# Steering_Board.net
KiCad netlist of a schematic drawn in EAGLE
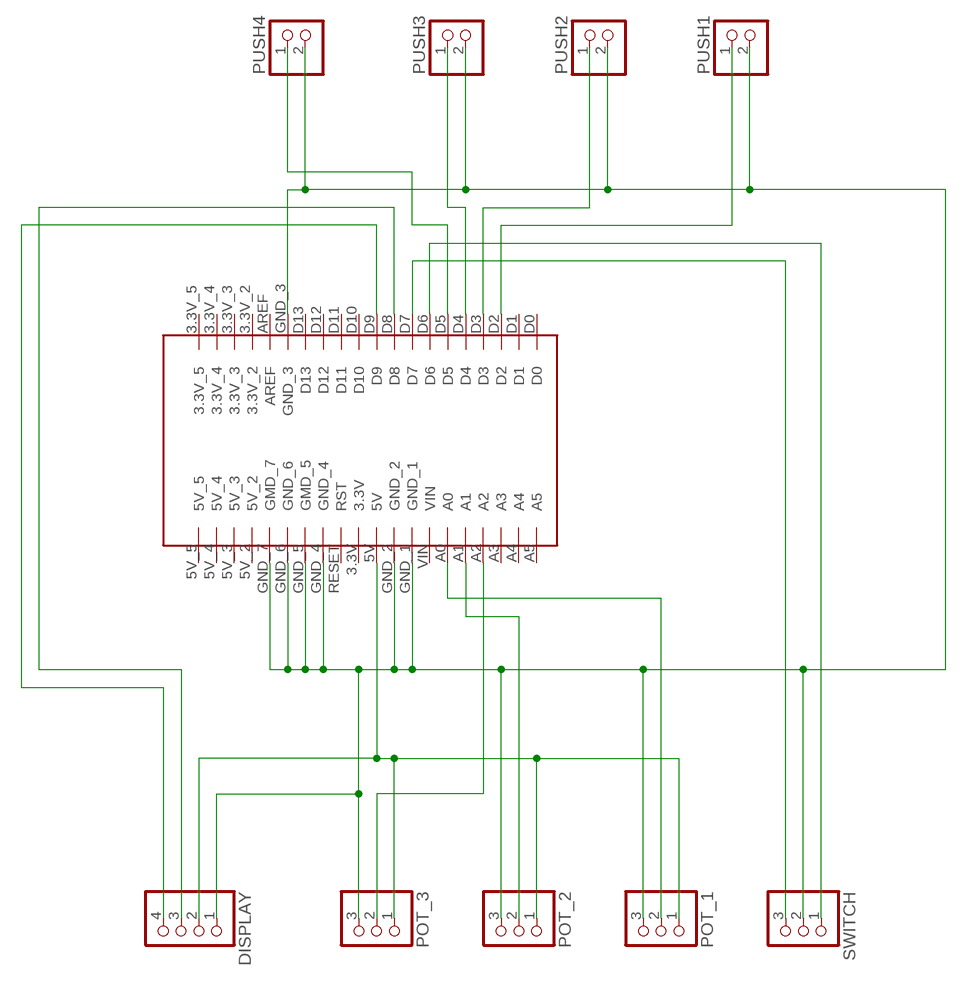
[diagram p0: schematic, sheet 1]

(export (version "E")
  (design (tool "Eeschema 10.0.6"))
  (components
    (comp (ref "2X40CONECTOR1")
      (value "2X40_CONNECTOR")
      (footprint "eagle-import:2X40_PIN_CONNECTOR")
      (libsource (lib "eagle-import") (part "2X40_CONNECTOR"))
    )
    (comp (ref "DISPLAY")
      (value "PINHD-1X4")
      (footprint "eagle-import:1X04")
      (libsource (lib "eagle-import") (part "PINHD-1X4"))
    )
    (comp (ref "POT_1")
      (value "PINHD-1X3")
      (footprint "eagle-import:1X03")
      (libsource (lib "eagle-import") (part "PINHD-1X3"))
    )
    (comp (ref "POT_2")
      (value "PINHD-1X3")
      (footprint "eagle-import:1X03")
      (libsource (lib "eagle-import") (part "PINHD-1X3"))
    )
    (comp (ref "POT_3")
      (value "PINHD-1X3")
      (footprint "eagle-import:1X03")
      (libsource (lib "eagle-import") (part "PINHD-1X3"))
    )
    (comp (ref "PUSH1")
      (value "PINHD-1X2")
      (footprint "eagle-import:1X02")
      (libsource (lib "eagle-import") (part "PINHD-1X2"))
    )
    (comp (ref "PUSH2")
      (value "PINHD-1X2")
      (footprint "eagle-import:1X02")
      (libsource (lib "eagle-import") (part "PINHD-1X2"))
    )
    (comp (ref "PUSH3")
      (value "PINHD-1X2")
      (footprint "eagle-import:1X02")
      (libsource (lib "eagle-import") (part "PINHD-1X2"))
    )
    (comp (ref "PUSH4")
      (value "PINHD-1X2")
      (footprint "eagle-import:1X02")
      (libsource (lib "eagle-import") (part "PINHD-1X2"))
    )
    (comp (ref "SWITCH")
      (value "PINHD-1X3")
      (footprint "eagle-import:1X03")
      (libsource (lib "eagle-import") (part "PINHD-1X3"))
    )
  )
  (nets
    (net (code "1") (name "Net-(2X40CONECTOR1-GMD_5)") (class "Default")
      (node (ref "2X40CONECTOR1") (pin "GND_1") (pinfunction "GND_1_GND_1") (pintype "bidirectional"))
      (node (ref "2X40CONECTOR1") (pin "GND_2") (pinfunction "GND_2_GND_2") (pintype "bidirectional"))
      (node (ref "2X40CONECTOR1") (pin "GND_3") (pinfunction "GND_3_GND_3") (pintype "bidirectional"))
      (node (ref "2X40CONECTOR1") (pin "GND_4") (pinfunction "GND_4_GND_4") (pintype "bidirectional"))
      (node (ref "2X40CONECTOR1") (pin "GND_5") (pinfunction "GMD_5_GND_5") (pintype "bidirectional"))
      (node (ref "2X40CONECTOR1") (pin "GND_6") (pinfunction "GND_6_GND_6") (pintype "bidirectional"))
      (node (ref "2X40CONECTOR1") (pin "GND_7") (pinfunction "GMD_7_GND_7") (pintype "bidirectional"))
      (node (ref "DISPLAY") (pin "1") (pinfunction "1_1") (pintype "passive"))
      (node (ref "POT_1") (pin "3") (pinfunction "3_3") (pintype "passive"))
      (node (ref "POT_2") (pin "3") (pinfunction "3_3") (pintype "passive"))
      (node (ref "POT_3") (pin "3") (pinfunction "3_3") (pintype "passive"))
      (node (ref "PUSH1") (pin "2") (pinfunction "2_2") (pintype "passive"))
      (node (ref "PUSH2") (pin "2") (pinfunction "2_2") (pintype "passive"))
      (node (ref "PUSH3") (pin "2") (pinfunction "2_2") (pintype "passive"))
      (node (ref "PUSH4") (pin "2") (pinfunction "2_2") (pintype "passive"))
      (node (ref "SWITCH") (pin "2") (pinfunction "2_2") (pintype "passive"))
    )
    (net (code "2") (name "Net-(2X40CONECTOR1-Pad5V)") (class "Default")
      (node (ref "2X40CONECTOR1") (pin "5V") (pinfunction "5V_5V") (pintype "bidirectional"))
      (node (ref "DISPLAY") (pin "2") (pinfunction "2_2") (pintype "passive"))
      (node (ref "POT_1") (pin "1") (pinfunction "1_1") (pintype "passive"))
      (node (ref "POT_2") (pin "1") (pinfunction "1_1") (pintype "passive"))
      (node (ref "POT_3") (pin "1") (pinfunction "1_1") (pintype "passive"))
    )
    (net (code "3") (name "Net-(2X40CONECTOR1-PadA0)") (class "Default")
      (node (ref "2X40CONECTOR1") (pin "A0") (pinfunction "A0_A0") (pintype "bidirectional"))
      (node (ref "POT_1") (pin "2") (pinfunction "2_2") (pintype "passive"))
    )
    (net (code "4") (name "Net-(2X40CONECTOR1-PadA1)") (class "Default")
      (node (ref "2X40CONECTOR1") (pin "A1") (pinfunction "A1_A1") (pintype "bidirectional"))
      (node (ref "POT_2") (pin "2") (pinfunction "2_2") (pintype "passive"))
    )
    (net (code "5") (name "Net-(2X40CONECTOR1-PadA2)") (class "Default")
      (node (ref "2X40CONECTOR1") (pin "A2") (pinfunction "A2_A2") (pintype "bidirectional"))
      (node (ref "POT_3") (pin "2") (pinfunction "2_2") (pintype "passive"))
    )
    (net (code "6") (name "Net-(2X40CONECTOR1-PadD2)") (class "Default")
      (node (ref "2X40CONECTOR1") (pin "D2") (pinfunction "D2_D2") (pintype "bidirectional"))
      (node (ref "PUSH1") (pin "1") (pinfunction "1_1") (pintype "passive"))
    )
    (net (code "7") (name "Net-(2X40CONECTOR1-PadD3)") (class "Default")
      (node (ref "2X40CONECTOR1") (pin "D3") (pinfunction "D3_D3") (pintype "bidirectional"))
      (node (ref "PUSH2") (pin "1") (pinfunction "1_1") (pintype "passive"))
    )
    (net (code "8") (name "Net-(2X40CONECTOR1-PadD4)") (class "Default")
      (node (ref "2X40CONECTOR1") (pin "D4") (pinfunction "D4_D4") (pintype "bidirectional"))
      (node (ref "PUSH3") (pin "1") (pinfunction "1_1") (pintype "passive"))
    )
    (net (code "9") (name "Net-(2X40CONECTOR1-PadD5)") (class "Default")
      (node (ref "2X40CONECTOR1") (pin "D5") (pinfunction "D5_D5") (pintype "bidirectional"))
      (node (ref "PUSH4") (pin "1") (pinfunction "1_1") (pintype "passive"))
    )
    (net (code "10") (name "Net-(2X40CONECTOR1-PadD6)") (class "Default")
      (node (ref "2X40CONECTOR1") (pin "D6") (pinfunction "D6_D6") (pintype "bidirectional"))
      (node (ref "SWITCH") (pin "1") (pinfunction "1_1") (pintype "passive"))
    )
    (net (code "11") (name "Net-(2X40CONECTOR1-PadD7)") (class "Default")
      (node (ref "2X40CONECTOR1") (pin "D7") (pinfunction "D7_D7") (pintype "bidirectional"))
      (node (ref "SWITCH") (pin "3") (pinfunction "3_3") (pintype "passive"))
    )
    (net (code "12") (name "Net-(2X40CONECTOR1-PadD8)") (class "Default")
      (node (ref "2X40CONECTOR1") (pin "D8") (pinfunction "D8_D8") (pintype "bidirectional"))
      (node (ref "DISPLAY") (pin "3") (pinfunction "3_3") (pintype "passive"))
    )
    (net (code "13") (name "Net-(2X40CONECTOR1-PadD9)") (class "Default")
      (node (ref "2X40CONECTOR1") (pin "D9") (pinfunction "D9_D9") (pintype "bidirectional"))
      (node (ref "DISPLAY") (pin "4") (pinfunction "4_4") (pintype "passive"))
    )
    (net (code "14") (name "unconnected-(2X40CONECTOR1-Pad3.3V)") (class "Default")
      (node (ref "2X40CONECTOR1") (pin "3.3V") (pinfunction "3.3V_3.3V") (pintype "bidirectional"))
    )
    (net (code "15") (name "unconnected-(2X40CONECTOR1-Pad3.3V_2)") (class "Default")
      (node (ref "2X40CONECTOR1") (pin "3.3V_2") (pinfunction "3.3V_2_3.3V_2") (pintype "bidirectional"))
    )
    (net (code "16") (name "unconnected-(2X40CONECTOR1-Pad3.3V_3)") (class "Default")
      (node (ref "2X40CONECTOR1") (pin "3.3V_3") (pinfunction "3.3V_3_3.3V_3") (pintype "bidirectional"))
    )
    (net (code "17") (name "unconnected-(2X40CONECTOR1-Pad3.3V_4)") (class "Default")
      (node (ref "2X40CONECTOR1") (pin "3.3V_4") (pinfunction "3.3V_4_3.3V_4") (pintype "bidirectional"))
    )
    (net (code "18") (name "unconnected-(2X40CONECTOR1-Pad3.3V_5)") (class "Default")
      (node (ref "2X40CONECTOR1") (pin "3.3V_5") (pinfunction "3.3V_5_3.3V_5") (pintype "bidirectional"))
    )
    (net (code "19") (name "unconnected-(2X40CONECTOR1-Pad5V_2)") (class "Default")
      (node (ref "2X40CONECTOR1") (pin "5V_2") (pinfunction "5V_2_5V_2") (pintype "bidirectional"))
    )
    (net (code "20") (name "unconnected-(2X40CONECTOR1-Pad5V_3)") (class "Default")
      (node (ref "2X40CONECTOR1") (pin "5V_3") (pinfunction "5V_3_5V_3") (pintype "bidirectional"))
    )
    (net (code "21") (name "unconnected-(2X40CONECTOR1-Pad5V_4)") (class "Default")
      (node (ref "2X40CONECTOR1") (pin "5V_4") (pinfunction "5V_4_5V_4") (pintype "bidirectional"))
    )
    (net (code "22") (name "unconnected-(2X40CONECTOR1-Pad5V_5)") (class "Default")
      (node (ref "2X40CONECTOR1") (pin "5V_5") (pinfunction "5V_5_5V_5") (pintype "bidirectional"))
    )
    (net (code "23") (name "unconnected-(2X40CONECTOR1-PadA3)") (class "Default")
      (node (ref "2X40CONECTOR1") (pin "A3") (pinfunction "A3_A3") (pintype "bidirectional"))
    )
    (net (code "24") (name "unconnected-(2X40CONECTOR1-PadA4)") (class "Default")
      (node (ref "2X40CONECTOR1") (pin "A4") (pinfunction "A4_A4") (pintype "bidirectional"))
    )
    (net (code "25") (name "unconnected-(2X40CONECTOR1-PadA5)") (class "Default")
      (node (ref "2X40CONECTOR1") (pin "A5") (pinfunction "A5_A5") (pintype "bidirectional"))
    )
    (net (code "26") (name "unconnected-(2X40CONECTOR1-PadAREF)") (class "Default")
      (node (ref "2X40CONECTOR1") (pin "AREF") (pinfunction "AREF_AREF") (pintype "bidirectional"))
    )
    (net (code "27") (name "unconnected-(2X40CONECTOR1-PadD0)") (class "Default")
      (node (ref "2X40CONECTOR1") (pin "D0") (pinfunction "D0_D0") (pintype "bidirectional"))
    )
    (net (code "28") (name "unconnected-(2X40CONECTOR1-PadD1)") (class "Default")
      (node (ref "2X40CONECTOR1") (pin "D1") (pinfunction "D1_D1") (pintype "bidirectional"))
    )
    (net (code "29") (name "unconnected-(2X40CONECTOR1-PadD10)") (class "Default")
      (node (ref "2X40CONECTOR1") (pin "D10") (pinfunction "D10_D10") (pintype "bidirectional"))
    )
    (net (code "30") (name "unconnected-(2X40CONECTOR1-PadD11)") (class "Default")
      (node (ref "2X40CONECTOR1") (pin "D11") (pinfunction "D11_D11") (pintype "bidirectional"))
    )
    (net (code "31") (name "unconnected-(2X40CONECTOR1-PadD12)") (class "Default")
      (node (ref "2X40CONECTOR1") (pin "D12") (pinfunction "D12_D12") (pintype "bidirectional"))
    )
    (net (code "32") (name "unconnected-(2X40CONECTOR1-PadD13)") (class "Default")
      (node (ref "2X40CONECTOR1") (pin "D13") (pinfunction "D13_D13") (pintype "bidirectional"))
    )
    (net (code "33") (name "unconnected-(2X40CONECTOR1-PadVIN)") (class "Default")
      (node (ref "2X40CONECTOR1") (pin "VIN") (pinfunction "VIN_VIN") (pintype "bidirectional"))
    )
    (net (code "34") (name "unconnected-(2X40CONECTOR1-RST-PadRESET)") (class "Default")
      (node (ref "2X40CONECTOR1") (pin "RESET") (pinfunction "RST_RESET") (pintype "bidirectional"))
    )
  )
)
